# ESP32C3.net
KiCad netlist of a schematic drawn in EasyEDA Pro
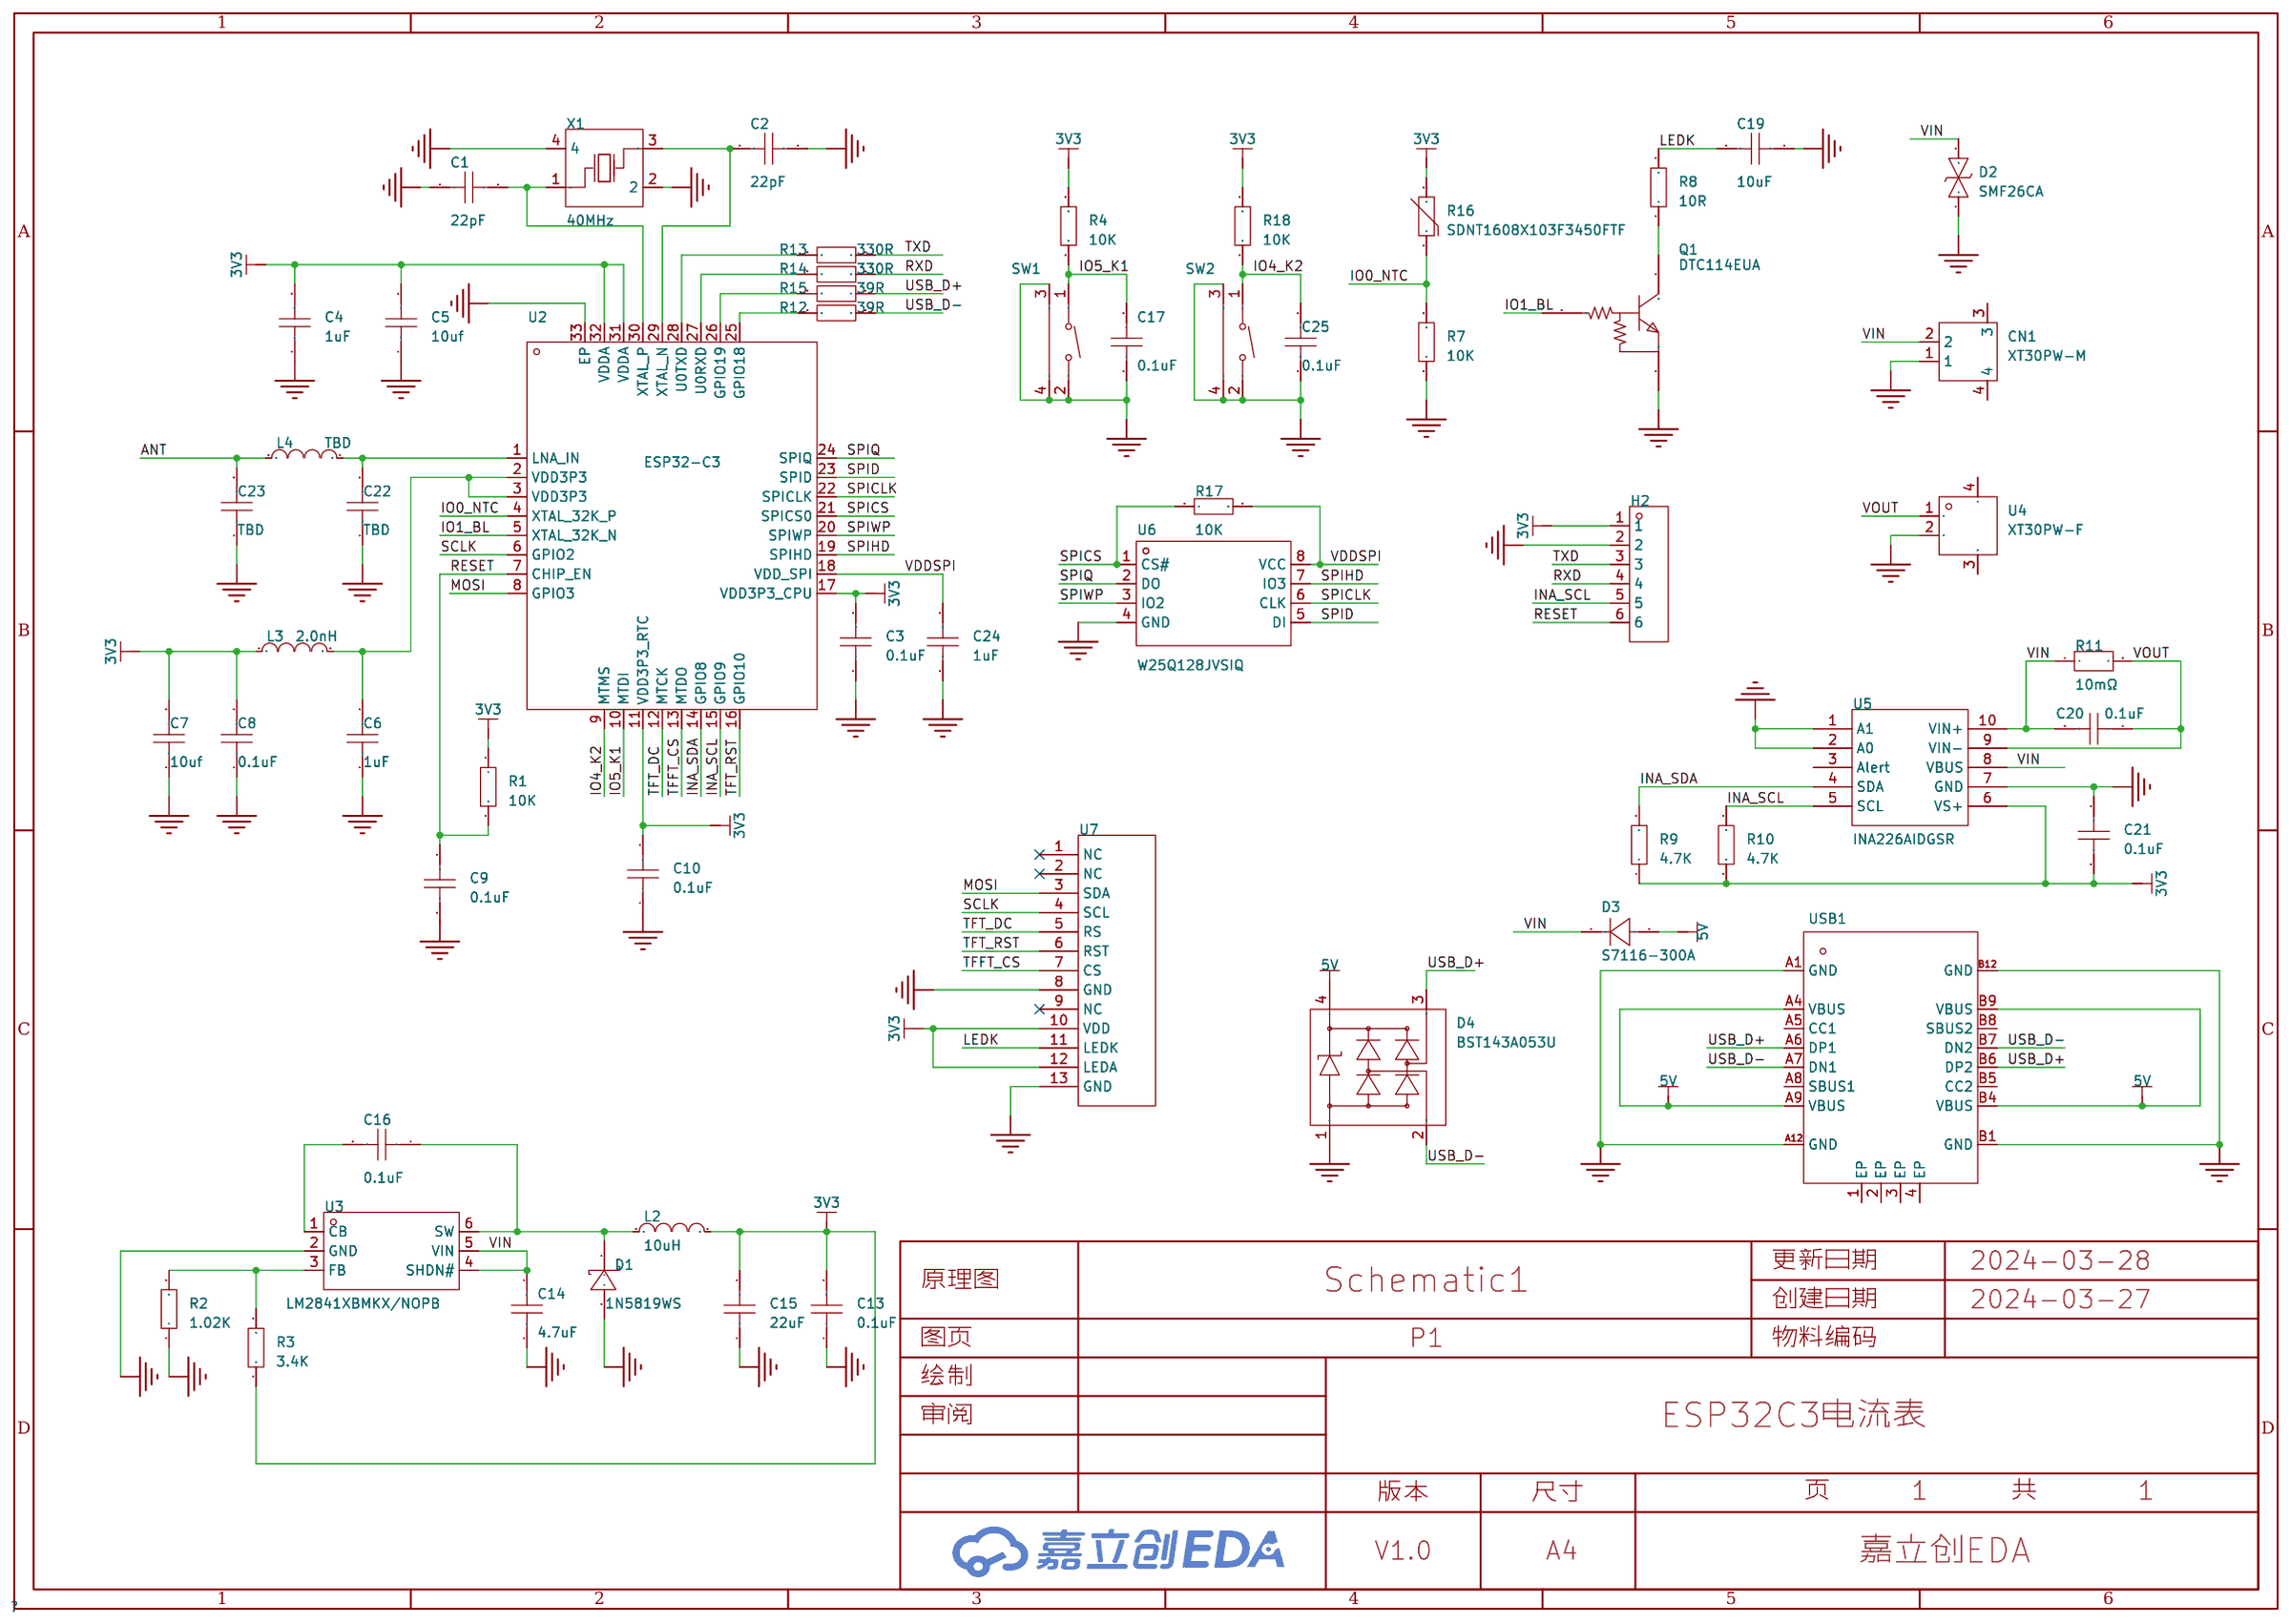
[diagram p0: schematic sheet]

(export (version "E")
  (design (tool "Eeschema 10.0.6"))
  (components
    (comp (ref "C1")
      (value "22pF")
      (footprint "easyedapro:C0805")
      (libsource (lib "easyedapro") (part "CapAcitance"))
    )
    (comp (ref "C2")
      (value "22pF")
      (footprint "easyedapro:C0805")
      (libsource (lib "easyedapro") (part "CapAcitance"))
    )
    (comp (ref "C3")
      (value "0.1uF")
      (footprint "easyedapro:C0805")
      (libsource (lib "easyedapro") (part "CapAcitance"))
    )
    (comp (ref "C4")
      (value "1uF")
      (footprint "easyedapro:C0805")
      (libsource (lib "easyedapro") (part "CapAcitance"))
    )
    (comp (ref "C5")
      (value "10uf")
      (footprint "easyedapro:C0805")
      (libsource (lib "easyedapro") (part "CapAcitance"))
    )
    (comp (ref "C6")
      (value "1uF")
      (footprint "easyedapro:C0805")
      (libsource (lib "easyedapro") (part "CapAcitance"))
    )
    (comp (ref "C7")
      (value "10uf")
      (footprint "easyedapro:C0805")
      (libsource (lib "easyedapro") (part "CapAcitance"))
    )
    (comp (ref "C8")
      (value "0.1uF")
      (footprint "easyedapro:C0805")
      (libsource (lib "easyedapro") (part "CapAcitance"))
    )
    (comp (ref "C9")
      (value "0.1uF")
      (footprint "easyedapro:C0805")
      (libsource (lib "easyedapro") (part "CapAcitance"))
    )
    (comp (ref "C10")
      (value "0.1uF")
      (footprint "easyedapro:C0805")
      (libsource (lib "easyedapro") (part "CapAcitance"))
    )
    (comp (ref "C13")
      (value "0.1uF")
      (footprint "easyedapro:C0805")
      (libsource (lib "easyedapro") (part "CapAcitance"))
    )
    (comp (ref "C14")
      (value "4.7uF")
      (footprint "easyedapro:C0805")
      (libsource (lib "easyedapro") (part "CapAcitance"))
    )
    (comp (ref "C15")
      (value "22uF")
      (footprint "easyedapro:C0805")
      (libsource (lib "easyedapro") (part "CapAcitance"))
    )
    (comp (ref "C16")
      (value "0.1uF")
      (footprint "easyedapro:C0805")
      (libsource (lib "easyedapro") (part "CapAcitance"))
    )
    (comp (ref "C17")
      (value "0.1uF")
      (footprint "easyedapro:C0805")
      (libsource (lib "easyedapro") (part "CapAcitance"))
    )
    (comp (ref "C19")
      (value "10uF")
      (footprint "easyedapro:C0805")
      (libsource (lib "easyedapro") (part "CapAcitance"))
    )
    (comp (ref "C20")
      (value "0.1uF")
      (footprint "easyedapro:C0805")
      (libsource (lib "easyedapro") (part "CapAcitance"))
    )
    (comp (ref "C21")
      (value "0.1uF")
      (footprint "easyedapro:C0805")
      (libsource (lib "easyedapro") (part "CapAcitance"))
    )
    (comp (ref "C22")
      (value "TBD")
      (footprint "easyedapro:C0805")
      (libsource (lib "easyedapro") (part "CapAcitance"))
    )
    (comp (ref "C23")
      (value "TBD")
      (footprint "easyedapro:C0805")
      (libsource (lib "easyedapro") (part "CapAcitance"))
    )
    (comp (ref "C24")
      (value "1uF")
      (footprint "easyedapro:C0805")
      (libsource (lib "easyedapro") (part "CapAcitance"))
    )
    (comp (ref "C25")
      (value "0.1uF")
      (footprint "easyedapro:C0805")
      (libsource (lib "easyedapro") (part "CapAcitance"))
    )
    (comp (ref "CN1")
      (value "XT30PW-M")
      (footprint "easyedapro:CONN-TH_XT30PW-M")
      (description "类别:-;类型1:-;")
      (fields (field (name "Manufacturer") "AMASS(艾迈斯)"))
      (libsource (lib "easyedapro") (part "XT30PW-M"))
    )
    (comp (ref "D1")
      (value "1N5819WS")
      (footprint "easyedapro:SOD-323_L1.8-W1.3-LS2.5-RD")
      (description "正向压降(Vf):600mV@1A;直流反向耐压(Vr):40V;平均整流电流(Io):1A;")
      (fields (field (name "Manufacturer") "Hottech(合科泰)"))
      (libsource (lib "easyedapro") (part "1N5819WS"))
    )
    (comp (ref "D2")
      (value "SMF26CA")
      (footprint "easyedapro:SOD-123_L2.8-W1.8-LS3.7-BI")
      (description "反向截止电压(Vrwm):26V;最大钳位电压:42.1V;峰值脉冲电流(Ipp)@10/1000us:4.8A;击穿电压:28.9V;")
      (fields (field (name "Manufacturer") "AnBon(安邦)"))
      (libsource (lib "easyedapro") (part "SMF26CA_C435495"))
    )
    (comp (ref "D3")
      (value "S7116-300A")
      (footprint "easyedapro:SOD-323_L1.7-W1.3-LS2.5-RD")
      (description "二极管配置:独立式;正向压降(Vf):500mV@1A;直流反向耐压(Vr):45V;平均整流电流(Io):1A;")
      (fields (field (name "Manufacturer") "MSKSEMI(美森科)"))
      (libsource (lib "easyedapro") (part "S7116-300A"))
    )
    (comp (ref "D4")
      (value "BST143A053U")
      (footprint "easyedapro:SOT-143_L2.9-W1.3-P1.92-LS2.3-BR")
      (description "反向截止电压(Vrwm):5V;最大钳位电压:25V;峰值脉冲电流(Ipp)@10/1000us:12A@8/20us;")
      (fields (field (name "Manufacturer") "BORN(伯恩半导体)"))
      (libsource (lib "easyedapro") (part "BST143A053U"))
    )
    (comp (ref "H2")
      (value "~")
      (footprint "easyedapro:HDR-TH_6P-P2.54-V-F")
      (libsource (lib "easyedapro") (part "Header-Female-2.54_1x6"))
    )
    (comp (ref "L2")
      (value "10uH")
      (footprint "easyedapro:IND-SMD_L2.5-W2.0_FHD252012S-6R8MT")
      (description "电感值:10uH;精度:±20%;额定电流:1A;饱和电流(Isat):1.35A;")
      (fields
        (field (name "Manufacturer Part") "FHD252012S-100MT")
        (field (name "Manufacturer") "cjiang(长江微电)")
      )
      (libsource (lib "easyedapro") (part "FHD252012S-100MT"))
    )
    (comp (ref "L3")
      (value "2.0nH")
      (footprint "easyedapro:L0603")
      (libsource (lib "easyedapro") (part "SDFL1608S100KTF"))
    )
    (comp (ref "L4")
      (value "TBD")
      (footprint "easyedapro:L0603")
      (libsource (lib "easyedapro") (part "SDFL1608S100KTF"))
    )
    (comp (ref "Q1")
      (value "DTC114EUA")
      (footprint "easyedapro:SOT-323-3_L2.0-W1.3-P1.30-LS2.1-BR")
      (description "晶体管类型:1个NPN-预偏置;集射极击穿电压(Vceo):50V;集电极电流(Ic):50mA;功率(Pd):200mW;")
      (fields (field (name "Manufacturer") "CJ(江苏长电/长晶)"))
      (libsource (lib "easyedapro") (part "DTC114EUA"))
    )
    (comp (ref "R1") (value "10K") (footprint "easyedapro:R0603") (libsource (lib "easyedapro") (part "电阻")))
    (comp (ref "R2")
      (value "1.02K")
      (footprint "easyedapro:R0603")
      (libsource (lib "easyedapro") (part "电阻"))
    )
    (comp (ref "R3") (value "3.4K") (footprint "easyedapro:R0603") (libsource (lib "easyedapro") (part "电阻")))
    (comp (ref "R4") (value "10K") (footprint "easyedapro:R0603") (libsource (lib "easyedapro") (part "电阻")))
    (comp (ref "R7") (value "10K") (footprint "easyedapro:R0603") (libsource (lib "easyedapro") (part "电阻")))
    (comp (ref "R8") (value "10R") (footprint "easyedapro:R0603") (libsource (lib "easyedapro") (part "电阻")))
    (comp (ref "R9") (value "4.7K") (footprint "easyedapro:R0603") (libsource (lib "easyedapro") (part "电阻")))
    (comp (ref "R10")
      (value "4.7K")
      (footprint "easyedapro:R0603")
      (libsource (lib "easyedapro") (part "电阻"))
    )
    (comp (ref "R11")
      (value "10mΩ")
      (footprint "easyedapro:R2512")
      (description "电阻类型:采样电阻;阻值:10mΩ;精度:±1%;额定压降:-;功率:3W;温度系数:±50ppm/°C;安装方式:-;")
      (fields (field (name "Manufacturer Part") "PA2512FKE7T0R01E") (field (name "Manufacturer") "YAGEO(国巨)"))
      (libsource (lib "easyedapro") (part "PA2512FKE7T0R01E"))
    )
    (comp (ref "R12") (value "39R") (footprint "easyedapro:R0603") (libsource (lib "easyedapro") (part "电阻")))
    (comp (ref "R13")
      (value "330R")
      (footprint "easyedapro:R0603")
      (libsource (lib "easyedapro") (part "电阻"))
    )
    (comp (ref "R14")
      (value "330R")
      (footprint "easyedapro:R0603")
      (libsource (lib "easyedapro") (part "电阻"))
    )
    (comp (ref "R15") (value "39R") (footprint "easyedapro:R0603") (libsource (lib "easyedapro") (part "电阻")))
    (comp (ref "R16")
      (value "SDNT1608X103F3450FTF")
      (footprint "easyedapro:R0603")
      (description "阻值(25°C):10kΩ;B值(25°C/50°C):3450K;电阻精度:±1%;功率:100mW;B值精度:±1%;最大稳态电流(25°C):310uA;")
      (fields (field (name "Manufacturer") "Sunlord(顺络)"))
      (libsource (lib "easyedapro") (part "SDNT1608X103F3450FTF"))
    )
    (comp (ref "R17") (value "10K") (footprint "easyedapro:R0603") (libsource (lib "easyedapro") (part "电阻")))
    (comp (ref "R18") (value "10K") (footprint "easyedapro:R0603") (libsource (lib "easyedapro") (part "电阻")))
    (comp (ref "SW1")
      (value "TS-1010-C-A")
      (footprint "easyedapro:KEY-SMD_TX-1010-X-X")
      (fields (field (name "Manufacturer") "XKB Connectivity(中国星坤)"))
      (libsource (lib "easyedapro") (part "TS-1010-C-A"))
    )
    (comp (ref "SW2")
      (value "TS-1010-C-A")
      (footprint "easyedapro:KEY-SMD_TX-1010-X-X")
      (fields (field (name "Manufacturer") "XKB Connectivity(中国星坤)"))
      (libsource (lib "easyedapro") (part "TS-1010-C-A"))
    )
    (comp (ref "U2")
      (value "ESP32-C3")
      (footprint "easyedapro:QFN-32_L5.0-W5.0-P0.50-TL-EP3.7")
      (description "CPU内核:RISC-V;RAM总容量:400KB;GPIO端口数量:22;工作电压范围:3V~3.6V;CPU最大主频:160MHz;程序存储器类型:-;")
      (fields (field (name "Manufacturer") "ESPRESSIF(乐鑫)"))
      (libsource (lib "easyedapro") (part "ESP32-C3"))
    )
    (comp (ref "U3")
      (value "LM2841XBMKX/NOPB")
      (footprint "easyedapro:SOT-23-6_L2.9-W1.6-P0.95-LS2.8-BR")
      (description "功能类型:降压型;输入电压:-;输出电流(最大值):-;")
      (fields (field (name "Manufacturer") "TI(德州仪器)"))
      (libsource (lib "easyedapro") (part "LM2841XBMKX/NOPB"))
    )
    (comp (ref "U4")
      (value "XT30PW-F")
      (footprint "easyedapro:CONN-TH_XT30PW-F-1")
      (description "类别:-;类型1:-;")
      (fields (field (name "Manufacturer") "AMASS(艾迈斯)"))
      (libsource (lib "easyedapro") (part "XT30PW-F"))
    )
    (comp (ref "U5")
      (value "INA226AIDGSR")
      (footprint "easyedapro:MSOP-10_L3.0-W3.0-P0.50-LS5.0-BL")
      (description "INA226 支持报警功能的 36V、双向、超高精度、低侧/高侧、I2C 输出电流/功率监控器")
      (fields (field (name "Manufacturer") "TI(德州仪器)"))
      (libsource (lib "easyedapro") (part "INA226AIDGSR"))
    )
    (comp (ref "U6")
      (value "W25Q128JVSIQ")
      (footprint "easyedapro:SOIC-8_L5.3-W5.3-P1.27-LS8.0-BL")
      (description "接口类型:-;存储容量:128Mbit;时钟频率(fc):-;")
      (fields (field (name "Manufacturer") "WINBOND(华邦)"))
      (libsource (lib "easyedapro") (part "W25Q128JVSIQTR"))
    )
    (comp (ref "U7") (value "~") (libsource (lib "easyedapro") (part "ST7789")))
    (comp (ref "USB1")
      (value "~")
      (footprint "easyedapro:USB_TYPE-C-16P")
      (libsource (lib "easyedapro") (part "USB_TYPE-C-16P"))
    )
    (comp (ref "X1")
      (value "40MHz")
      (footprint "easyedapro:OSC-SMD_4P-L3.2-W2.5-BL")
      (description "晶振类型:-;频率:-;外接负载电容:-;")
      (fields (field (name "Manufacturer Part") "1ZNY12000AB0C") (field (name "Manufacturer") "KDS(大真空)"))
      (libsource (lib "easyedapro") (part "1ZNY12000AB0C"))
    )
  )
  (nets
    (net (code "1") (name "/ANT") (class "Default")
      (node (ref "C23") (pin "2") (pinfunction "2_2") (pintype "input"))
      (node (ref "L4") (pin "1") (pinfunction "1_1") (pintype "unspecified"))
    )
    (net (code "2") (name "/INA_SCL") (class "Default")
      (node (ref "H2") (pin "5") (pinfunction "5_5") (pintype "unspecified"))
      (node (ref "R10") (pin "2") (pinfunction "2_2") (pintype "input"))
      (node (ref "U2") (pin "15") (pinfunction "GPIO9_15") (pintype "unspecified"))
      (node (ref "U5") (pin "5") (pinfunction "SCL_5") (pintype "unspecified"))
    )
    (net (code "3") (name "/INA_SDA") (class "Default")
      (node (ref "R9") (pin "2") (pinfunction "2_2") (pintype "input"))
      (node (ref "U2") (pin "14") (pinfunction "GPIO8_14") (pintype "unspecified"))
      (node (ref "U5") (pin "4") (pinfunction "SDA_4") (pintype "unspecified"))
    )
    (net (code "4") (name "/IO0_NTC") (class "Default")
      (node (ref "R16") (pin "1") (pinfunction "1_1") (pintype "input"))
      (node (ref "R7") (pin "2") (pinfunction "2_2") (pintype "input"))
      (node (ref "U2") (pin "4") (pinfunction "XTAL_32K_P_4") (pintype "unspecified"))
    )
    (net (code "5") (name "/IO1_BL") (class "Default")
      (node (ref "Q1") (pin "1") (pinfunction "IN_1") (pintype "unspecified"))
      (node (ref "U2") (pin "5") (pinfunction "XTAL_32K_N_5") (pintype "unspecified"))
    )
    (net (code "6") (name "/IO4_K2") (class "Default")
      (node (ref "C25") (pin "2") (pinfunction "2_2") (pintype "input"))
      (node (ref "R18") (pin "1") (pinfunction "1_1") (pintype "input"))
      (node (ref "SW2") (pin "1") (pinfunction "1_1") (pintype "unspecified"))
      (node (ref "U2") (pin "9") (pinfunction "MTMS_9") (pintype "unspecified"))
    )
    (net (code "7") (name "/IO5_K1") (class "Default")
      (node (ref "C17") (pin "2") (pinfunction "2_2") (pintype "input"))
      (node (ref "R4") (pin "1") (pinfunction "1_1") (pintype "input"))
      (node (ref "SW1") (pin "1") (pinfunction "1_1") (pintype "unspecified"))
      (node (ref "U2") (pin "10") (pinfunction "MTDI_10") (pintype "unspecified"))
    )
    (net (code "8") (name "/LEDK") (class "Default")
      (node (ref "C19") (pin "2") (pinfunction "2_2") (pintype "input"))
      (node (ref "R8") (pin "2") (pinfunction "2_2") (pintype "input"))
      (node (ref "U7") (pin "11") (pinfunction "LEDK_11") (pintype "input"))
    )
    (net (code "9") (name "/MOSI") (class "Default")
      (node (ref "U2") (pin "8") (pinfunction "GPIO3_8") (pintype "unspecified"))
      (node (ref "U7") (pin "3") (pinfunction "SDA_3") (pintype "input"))
    )
    (net (code "10") (name "/RESET") (class "Default")
      (node (ref "C9") (pin "1") (pinfunction "1_1") (pintype "input"))
      (node (ref "H2") (pin "6") (pinfunction "6_6") (pintype "unspecified"))
      (node (ref "R1") (pin "2") (pinfunction "2_2") (pintype "input"))
      (node (ref "U2") (pin "7") (pinfunction "CHIP_EN_7") (pintype "unspecified"))
    )
    (net (code "11") (name "/RXD") (class "Default")
      (node (ref "H2") (pin "4") (pinfunction "4_4") (pintype "unspecified"))
      (node (ref "R14") (pin "1") (pinfunction "1_1") (pintype "input"))
    )
    (net (code "12") (name "/SCLK") (class "Default")
      (node (ref "U2") (pin "6") (pinfunction "GPIO2_6") (pintype "unspecified"))
      (node (ref "U7") (pin "4") (pinfunction "SCL_4") (pintype "input"))
    )
    (net (code "13") (name "/SPICLK") (class "Default")
      (node (ref "U2") (pin "22") (pinfunction "SPICLK_22") (pintype "unspecified"))
      (node (ref "U6") (pin "6") (pinfunction "CLK_6") (pintype "unspecified"))
    )
    (net (code "14") (name "/SPICS") (class "Default")
      (node (ref "R17") (pin "1") (pinfunction "1_1") (pintype "input"))
      (node (ref "U2") (pin "21") (pinfunction "SPICS0_21") (pintype "unspecified"))
      (node (ref "U6") (pin "1") (pinfunction "CS#_1") (pintype "unspecified"))
    )
    (net (code "15") (name "/SPID") (class "Default")
      (node (ref "U2") (pin "23") (pinfunction "SPID_23") (pintype "unspecified"))
      (node (ref "U6") (pin "5") (pinfunction "DI_5") (pintype "unspecified"))
    )
    (net (code "16") (name "/SPIHD") (class "Default")
      (node (ref "U2") (pin "19") (pinfunction "SPIHD_19") (pintype "unspecified"))
      (node (ref "U6") (pin "7") (pinfunction "IO3_7") (pintype "unspecified"))
    )
    (net (code "17") (name "/SPIQ") (class "Default")
      (node (ref "U2") (pin "24") (pinfunction "SPIQ_24") (pintype "unspecified"))
      (node (ref "U6") (pin "2") (pinfunction "DO_2") (pintype "unspecified"))
    )
    (net (code "18") (name "/SPIWP") (class "Default")
      (node (ref "U2") (pin "20") (pinfunction "SPIWP_20") (pintype "unspecified"))
      (node (ref "U6") (pin "3") (pinfunction "IO2_3") (pintype "unspecified"))
    )
    (net (code "19") (name "/TFFT_CS") (class "Default")
      (node (ref "U2") (pin "13") (pinfunction "MTDO_13") (pintype "unspecified"))
      (node (ref "U7") (pin "7") (pinfunction "CS_7") (pintype "input"))
    )
    (net (code "20") (name "/TFT_DC") (class "Default")
      (node (ref "U2") (pin "12") (pinfunction "MTCK_12") (pintype "unspecified"))
      (node (ref "U7") (pin "5") (pinfunction "RS_5") (pintype "input"))
    )
    (net (code "21") (name "/TFT_RST") (class "Default")
      (node (ref "U2") (pin "16") (pinfunction "GPIO10_16") (pintype "unspecified"))
      (node (ref "U7") (pin "6") (pinfunction "RST_6") (pintype "input"))
    )
    (net (code "22") (name "/TXD") (class "Default")
      (node (ref "H2") (pin "3") (pinfunction "3_3") (pintype "unspecified"))
      (node (ref "R13") (pin "1") (pinfunction "1_1") (pintype "input"))
    )
    (net (code "23") (name "/USB_D+") (class "Default")
      (node (ref "D4") (pin "3") (pinfunction "3_3") (pintype "unspecified"))
      (node (ref "R15") (pin "1") (pinfunction "1_1") (pintype "input"))
      (node (ref "USB1") (pin "A6") (pinfunction "DP1_A6") (pintype "input"))
      (node (ref "USB1") (pin "B6") (pinfunction "DP2_B6") (pintype "input"))
    )
    (net (code "24") (name "/USB_D-") (class "Default")
      (node (ref "D4") (pin "2") (pinfunction "2_2") (pintype "unspecified"))
      (node (ref "R12") (pin "1") (pinfunction "1_1") (pintype "input"))
      (node (ref "USB1") (pin "A7") (pinfunction "DN1_A7") (pintype "input"))
      (node (ref "USB1") (pin "B7") (pinfunction "DN2_B7") (pintype "input"))
    )
    (net (code "25") (name "/VDDSPI") (class "Default")
      (node (ref "C24") (pin "2") (pinfunction "2_2") (pintype "input"))
      (node (ref "R17") (pin "2") (pinfunction "2_2") (pintype "input"))
      (node (ref "U2") (pin "18") (pinfunction "VDD_SPI_18") (pintype "unspecified"))
      (node (ref "U6") (pin "8") (pinfunction "VCC_8") (pintype "unspecified"))
    )
    (net (code "26") (name "/VIN") (class "Default")
      (node (ref "C14") (pin "2") (pinfunction "2_2") (pintype "input"))
      (node (ref "C20") (pin "2") (pinfunction "2_2") (pintype "input"))
      (node (ref "CN1") (pin "2") (pinfunction "2_2") (pintype "unspecified"))
      (node (ref "D2") (pin "2") (pinfunction "2_2") (pintype "unspecified"))
      (node (ref "D3") (pin "1") (pinfunction "K_1") (pintype "unspecified"))
      (node (ref "R11") (pin "1") (pinfunction "1_1") (pintype "unspecified"))
      (node (ref "U3") (pin "4") (pinfunction "SHDN#_4") (pintype "unspecified"))
      (node (ref "U3") (pin "5") (pinfunction "VIN_5") (pintype "unspecified"))
      (node (ref "U5") (pin "10") (pinfunction "VIN+_10") (pintype "unspecified"))
      (node (ref "U5") (pin "8") (pinfunction "VBUS_8") (pintype "unspecified"))
    )
    (net (code "27") (name "/VOUT") (class "Default")
      (node (ref "C20") (pin "1") (pinfunction "1_1") (pintype "input"))
      (node (ref "R11") (pin "2") (pinfunction "2_2") (pintype "unspecified"))
      (node (ref "U4") (pin "1") (pinfunction "1_1") (pintype "unspecified"))
      (node (ref "U5") (pin "9") (pinfunction "VIN-_9") (pintype "unspecified"))
    )
    (net (code "28") (name "3V3") (class "Default")
      (node (ref "C10") (pin "2") (pinfunction "2_2") (pintype "input"))
      (node (ref "C13") (pin "2") (pinfunction "2_2") (pintype "input"))
      (node (ref "C15") (pin "2") (pinfunction "2_2") (pintype "input"))
      (node (ref "C21") (pin "2") (pinfunction "2_2") (pintype "input"))
      (node (ref "C3") (pin "2") (pinfunction "2_2") (pintype "input"))
      (node (ref "C4") (pin "2") (pinfunction "2_2") (pintype "input"))
      (node (ref "C5") (pin "2") (pinfunction "2_2") (pintype "input"))
      (node (ref "C7") (pin "2") (pinfunction "2_2") (pintype "input"))
      (node (ref "C8") (pin "2") (pinfunction "2_2") (pintype "input"))
      (node (ref "H2") (pin "1") (pinfunction "1_1") (pintype "unspecified"))
      (node (ref "L2") (pin "2") (pinfunction "2_2") (pintype "unspecified"))
      (node (ref "L3") (pin "1") (pinfunction "1_1") (pintype "unspecified"))
      (node (ref "R1") (pin "1") (pinfunction "1_1") (pintype "input"))
      (node (ref "R10") (pin "1") (pinfunction "1_1") (pintype "input"))
      (node (ref "R16") (pin "2") (pinfunction "2_2") (pintype "input"))
      (node (ref "R18") (pin "2") (pinfunction "2_2") (pintype "input"))
      (node (ref "R3") (pin "1") (pinfunction "1_1") (pintype "input"))
      (node (ref "R4") (pin "2") (pinfunction "2_2") (pintype "input"))
      (node (ref "R9") (pin "1") (pinfunction "1_1") (pintype "input"))
      (node (ref "U2") (pin "11") (pinfunction "VDD3P3_RTC_11") (pintype "unspecified"))
      (node (ref "U2") (pin "17") (pinfunction "VDD3P3_CPU_17") (pintype "unspecified"))
      (node (ref "U2") (pin "31") (pinfunction "VDDA_31") (pintype "unspecified"))
      (node (ref "U2") (pin "32") (pinfunction "VDDA_32") (pintype "unspecified"))
      (node (ref "U5") (pin "6") (pinfunction "VS+_6") (pintype "unspecified"))
      (node (ref "U7") (pin "10") (pinfunction "VDD_10") (pintype "input"))
      (node (ref "U7") (pin "12") (pinfunction "LEDA_12") (pintype "input"))
    )
    (net (code "29") (name "5V") (class "Default")
      (node (ref "D3") (pin "2") (pinfunction "A_2") (pintype "unspecified"))
      (node (ref "D4") (pin "4") (pinfunction "4_4") (pintype "unspecified"))
      (node (ref "USB1") (pin "A4") (pinfunction "VBUS_A4") (pintype "input"))
      (node (ref "USB1") (pin "A9") (pinfunction "VBUS_A9") (pintype "input"))
      (node (ref "USB1") (pin "B4") (pinfunction "VBUS_B4") (pintype "input"))
      (node (ref "USB1") (pin "B9") (pinfunction "VBUS_B9") (pintype "input"))
    )
    (net (code "30") (name "GND") (class "Default")
      (node (ref "C1") (pin "1") (pinfunction "1_1") (pintype "input"))
      (node (ref "C10") (pin "1") (pinfunction "1_1") (pintype "input"))
      (node (ref "C13") (pin "1") (pinfunction "1_1") (pintype "input"))
      (node (ref "C14") (pin "1") (pinfunction "1_1") (pintype "input"))
      (node (ref "C15") (pin "1") (pinfunction "1_1") (pintype "input"))
      (node (ref "C17") (pin "1") (pinfunction "1_1") (pintype "input"))
      (node (ref "C19") (pin "1") (pinfunction "1_1") (pintype "input"))
      (node (ref "C2") (pin "2") (pinfunction "2_2") (pintype "input"))
      (node (ref "C21") (pin "1") (pinfunction "1_1") (pintype "input"))
      (node (ref "C22") (pin "1") (pinfunction "1_1") (pintype "input"))
      (node (ref "C23") (pin "1") (pinfunction "1_1") (pintype "input"))
      (node (ref "C24") (pin "1") (pinfunction "1_1") (pintype "input"))
      (node (ref "C25") (pin "1") (pinfunction "1_1") (pintype "input"))
      (node (ref "C3") (pin "1") (pinfunction "1_1") (pintype "input"))
      (node (ref "C4") (pin "1") (pinfunction "1_1") (pintype "input"))
      (node (ref "C5") (pin "1") (pinfunction "1_1") (pintype "input"))
      (node (ref "C6") (pin "1") (pinfunction "1_1") (pintype "input"))
      (node (ref "C7") (pin "1") (pinfunction "1_1") (pintype "input"))
      (node (ref "C8") (pin "1") (pinfunction "1_1") (pintype "input"))
      (node (ref "C9") (pin "2") (pinfunction "2_2") (pintype "input"))
      (node (ref "CN1") (pin "1") (pinfunction "1_1") (pintype "unspecified"))
      (node (ref "D1") (pin "2") (pinfunction "A_2") (pintype "unspecified"))
      (node (ref "D2") (pin "1") (pinfunction "1_1") (pintype "unspecified"))
      (node (ref "D4") (pin "1") (pinfunction "1_1") (pintype "unspecified"))
      (node (ref "H2") (pin "2") (pinfunction "2_2") (pintype "unspecified"))
      (node (ref "Q1") (pin "2") (pinfunction "GND_2") (pintype "unspecified"))
      (node (ref "R2") (pin "1") (pinfunction "1_1") (pintype "input"))
      (node (ref "R7") (pin "1") (pinfunction "1_1") (pintype "input"))
      (node (ref "SW1") (pin "2") (pinfunction "2_2") (pintype "unspecified"))
      (node (ref "SW1") (pin "3") (pinfunction "3_3") (pintype "unspecified"))
      (node (ref "SW1") (pin "4") (pinfunction "4_4") (pintype "unspecified"))
      (node (ref "SW2") (pin "2") (pinfunction "2_2") (pintype "unspecified"))
      (node (ref "SW2") (pin "3") (pinfunction "3_3") (pintype "unspecified"))
      (node (ref "SW2") (pin "4") (pinfunction "4_4") (pintype "unspecified"))
      (node (ref "U2") (pin "33") (pinfunction "EP_33") (pintype "unspecified"))
      (node (ref "U3") (pin "2") (pinfunction "GND_2") (pintype "unspecified"))
      (node (ref "U4") (pin "2") (pinfunction "2_2") (pintype "unspecified"))
      (node (ref "U5") (pin "1") (pinfunction "A1_1") (pintype "unspecified"))
      (node (ref "U5") (pin "2") (pinfunction "A0_2") (pintype "unspecified"))
      (node (ref "U5") (pin "7") (pinfunction "GND_7") (pintype "unspecified"))
      (node (ref "U6") (pin "4") (pinfunction "GND_4") (pintype "unspecified"))
      (node (ref "U7") (pin "13") (pinfunction "GND_13") (pintype "input"))
      (node (ref "U7") (pin "8") (pinfunction "GND_8") (pintype "input"))
      (node (ref "USB1") (pin "A1") (pinfunction "GND_A1") (pintype "input"))
      (node (ref "USB1") (pin "A12") (pinfunction "GND_A12") (pintype "input"))
      (node (ref "USB1") (pin "B1") (pinfunction "GND_B1") (pintype "input"))
      (node (ref "USB1") (pin "B12") (pinfunction "GND_B12") (pintype "input"))
      (node (ref "X1") (pin "2") (pinfunction "2_2") (pintype "input"))
      (node (ref "X1") (pin "4") (pinfunction "4_4") (pintype "input"))
    )
    (net (code "31") (name "Net-(C6-Pad2)") (class "Default")
      (node (ref "C6") (pin "2") (pinfunction "2_2") (pintype "input"))
      (node (ref "L3") (pin "2") (pinfunction "2_2") (pintype "unspecified"))
      (node (ref "U2") (pin "2") (pinfunction "VDD3P3_2") (pintype "unspecified"))
      (node (ref "U2") (pin "3") (pinfunction "VDD3P3_3") (pintype "unspecified"))
    )
    (net (code "32") (name "Net-(D1-K)") (class "Default")
      (node (ref "C16") (pin "1") (pinfunction "1_1") (pintype "input"))
      (node (ref "D1") (pin "1") (pinfunction "K_1") (pintype "unspecified"))
      (node (ref "L2") (pin "1") (pinfunction "1_1") (pintype "unspecified"))
      (node (ref "U3") (pin "6") (pinfunction "SW_6") (pintype "unspecified"))
    )
    (net (code "33") (name "Net-(Q1-OUT)") (class "Default")
      (node (ref "Q1") (pin "3") (pinfunction "OUT_3") (pintype "unspecified"))
      (node (ref "R8") (pin "1") (pinfunction "1_1") (pintype "input"))
    )
    (net (code "34") (name "Net-(U2-GPIO18)") (class "Default")
      (node (ref "R12") (pin "2") (pinfunction "2_2") (pintype "input"))
      (node (ref "U2") (pin "25") (pinfunction "GPIO18_25") (pintype "unspecified"))
    )
    (net (code "35") (name "Net-(U2-GPIO19)") (class "Default")
      (node (ref "R15") (pin "2") (pinfunction "2_2") (pintype "input"))
      (node (ref "U2") (pin "26") (pinfunction "GPIO19_26") (pintype "unspecified"))
    )
    (net (code "36") (name "Net-(U2-LNA_IN)") (class "Default")
      (node (ref "C22") (pin "2") (pinfunction "2_2") (pintype "input"))
      (node (ref "L4") (pin "2") (pinfunction "2_2") (pintype "unspecified"))
      (node (ref "U2") (pin "1") (pinfunction "LNA_IN_1") (pintype "unspecified"))
    )
    (net (code "37") (name "Net-(U2-U0RXD)") (class "Default")
      (node (ref "R14") (pin "2") (pinfunction "2_2") (pintype "input"))
      (node (ref "U2") (pin "27") (pinfunction "U0RXD_27") (pintype "unspecified"))
    )
    (net (code "38") (name "Net-(U2-U0TXD)") (class "Default")
      (node (ref "R13") (pin "2") (pinfunction "2_2") (pintype "input"))
      (node (ref "U2") (pin "28") (pinfunction "U0TXD_28") (pintype "unspecified"))
    )
    (net (code "39") (name "Net-(U2-XTAL_N)") (class "Default")
      (node (ref "C2") (pin "1") (pinfunction "1_1") (pintype "input"))
      (node (ref "U2") (pin "29") (pinfunction "XTAL_N_29") (pintype "unspecified"))
      (node (ref "X1") (pin "3") (pinfunction "OSC2_3") (pintype "input"))
    )
    (net (code "40") (name "Net-(U2-XTAL_P)") (class "Default")
      (node (ref "C1") (pin "2") (pinfunction "2_2") (pintype "input"))
      (node (ref "U2") (pin "30") (pinfunction "XTAL_P_30") (pintype "unspecified"))
      (node (ref "X1") (pin "1") (pinfunction "OSC1_1") (pintype "input"))
    )
    (net (code "41") (name "Net-(U3-CB)") (class "Default")
      (node (ref "C16") (pin "2") (pinfunction "2_2") (pintype "input"))
      (node (ref "U3") (pin "1") (pinfunction "CB_1") (pintype "unspecified"))
    )
    (net (code "42") (name "Net-(U3-FB)") (class "Default")
      (node (ref "R2") (pin "2") (pinfunction "2_2") (pintype "input"))
      (node (ref "R3") (pin "2") (pinfunction "2_2") (pintype "input"))
      (node (ref "U3") (pin "3") (pinfunction "FB_3") (pintype "unspecified"))
    )
    (net (code "43") (name "unconnected-(CN1-Pad3)") (class "Default")
      (node (ref "CN1") (pin "3") (pinfunction "3_3") (pintype "unspecified"))
    )
    (net (code "44") (name "unconnected-(CN1-Pad4)") (class "Default")
      (node (ref "CN1") (pin "4") (pinfunction "4_4") (pintype "unspecified"))
    )
    (net (code "45") (name "unconnected-(U4-Pad3)") (class "Default")
      (node (ref "U4") (pin "3") (pinfunction "3_3") (pintype "unspecified"))
    )
    (net (code "46") (name "unconnected-(U4-Pad4)") (class "Default")
      (node (ref "U4") (pin "4") (pinfunction "4_4") (pintype "unspecified"))
    )
    (net (code "47") (name "unconnected-(U5-Alert-Pad3)") (class "Default")
      (node (ref "U5") (pin "3") (pinfunction "Alert_3") (pintype "unspecified"))
    )
    (net (code "48") (name "unconnected-(U7-NC-Pad1)") (class "Default")
      (node (ref "U7") (pin "1") (pinfunction "NC_1") (pintype "input+no_connect"))
    )
    (net (code "49") (name "unconnected-(U7-NC-Pad2)") (class "Default")
      (node (ref "U7") (pin "2") (pinfunction "NC_2") (pintype "input+no_connect"))
    )
    (net (code "50") (name "unconnected-(U7-NC-Pad9)") (class "Default")
      (node (ref "U7") (pin "9") (pinfunction "NC_9") (pintype "input+no_connect"))
    )
    (net (code "51") (name "unconnected-(USB1-CC1-PadA5)") (class "Default")
      (node (ref "USB1") (pin "A5") (pinfunction "CC1_A5") (pintype "input"))
    )
    (net (code "52") (name "unconnected-(USB1-CC2-PadB5)") (class "Default")
      (node (ref "USB1") (pin "B5") (pinfunction "CC2_B5") (pintype "input"))
    )
    (net (code "53") (name "unconnected-(USB1-EP-Pad1)") (class "Default")
      (node (ref "USB1") (pin "1") (pinfunction "EP_1") (pintype "input"))
    )
    (net (code "54") (name "unconnected-(USB1-EP-Pad2)") (class "Default")
      (node (ref "USB1") (pin "2") (pinfunction "EP_2") (pintype "input"))
    )
    (net (code "55") (name "unconnected-(USB1-EP-Pad3)") (class "Default")
      (node (ref "USB1") (pin "3") (pinfunction "EP_3") (pintype "input"))
    )
    (net (code "56") (name "unconnected-(USB1-EP-Pad4)") (class "Default")
      (node (ref "USB1") (pin "4") (pinfunction "EP_4") (pintype "input"))
    )
    (net (code "57") (name "unconnected-(USB1-SBUS1-PadA8)") (class "Default")
      (node (ref "USB1") (pin "A8") (pinfunction "SBUS1_A8") (pintype "input"))
    )
    (net (code "58") (name "unconnected-(USB1-SBUS2-PadB8)") (class "Default")
      (node (ref "USB1") (pin "B8") (pinfunction "SBUS2_B8") (pintype "input"))
    )
  )
)
